# DAC.net
KiCad netlist of a schematic drawn in Altium Designer
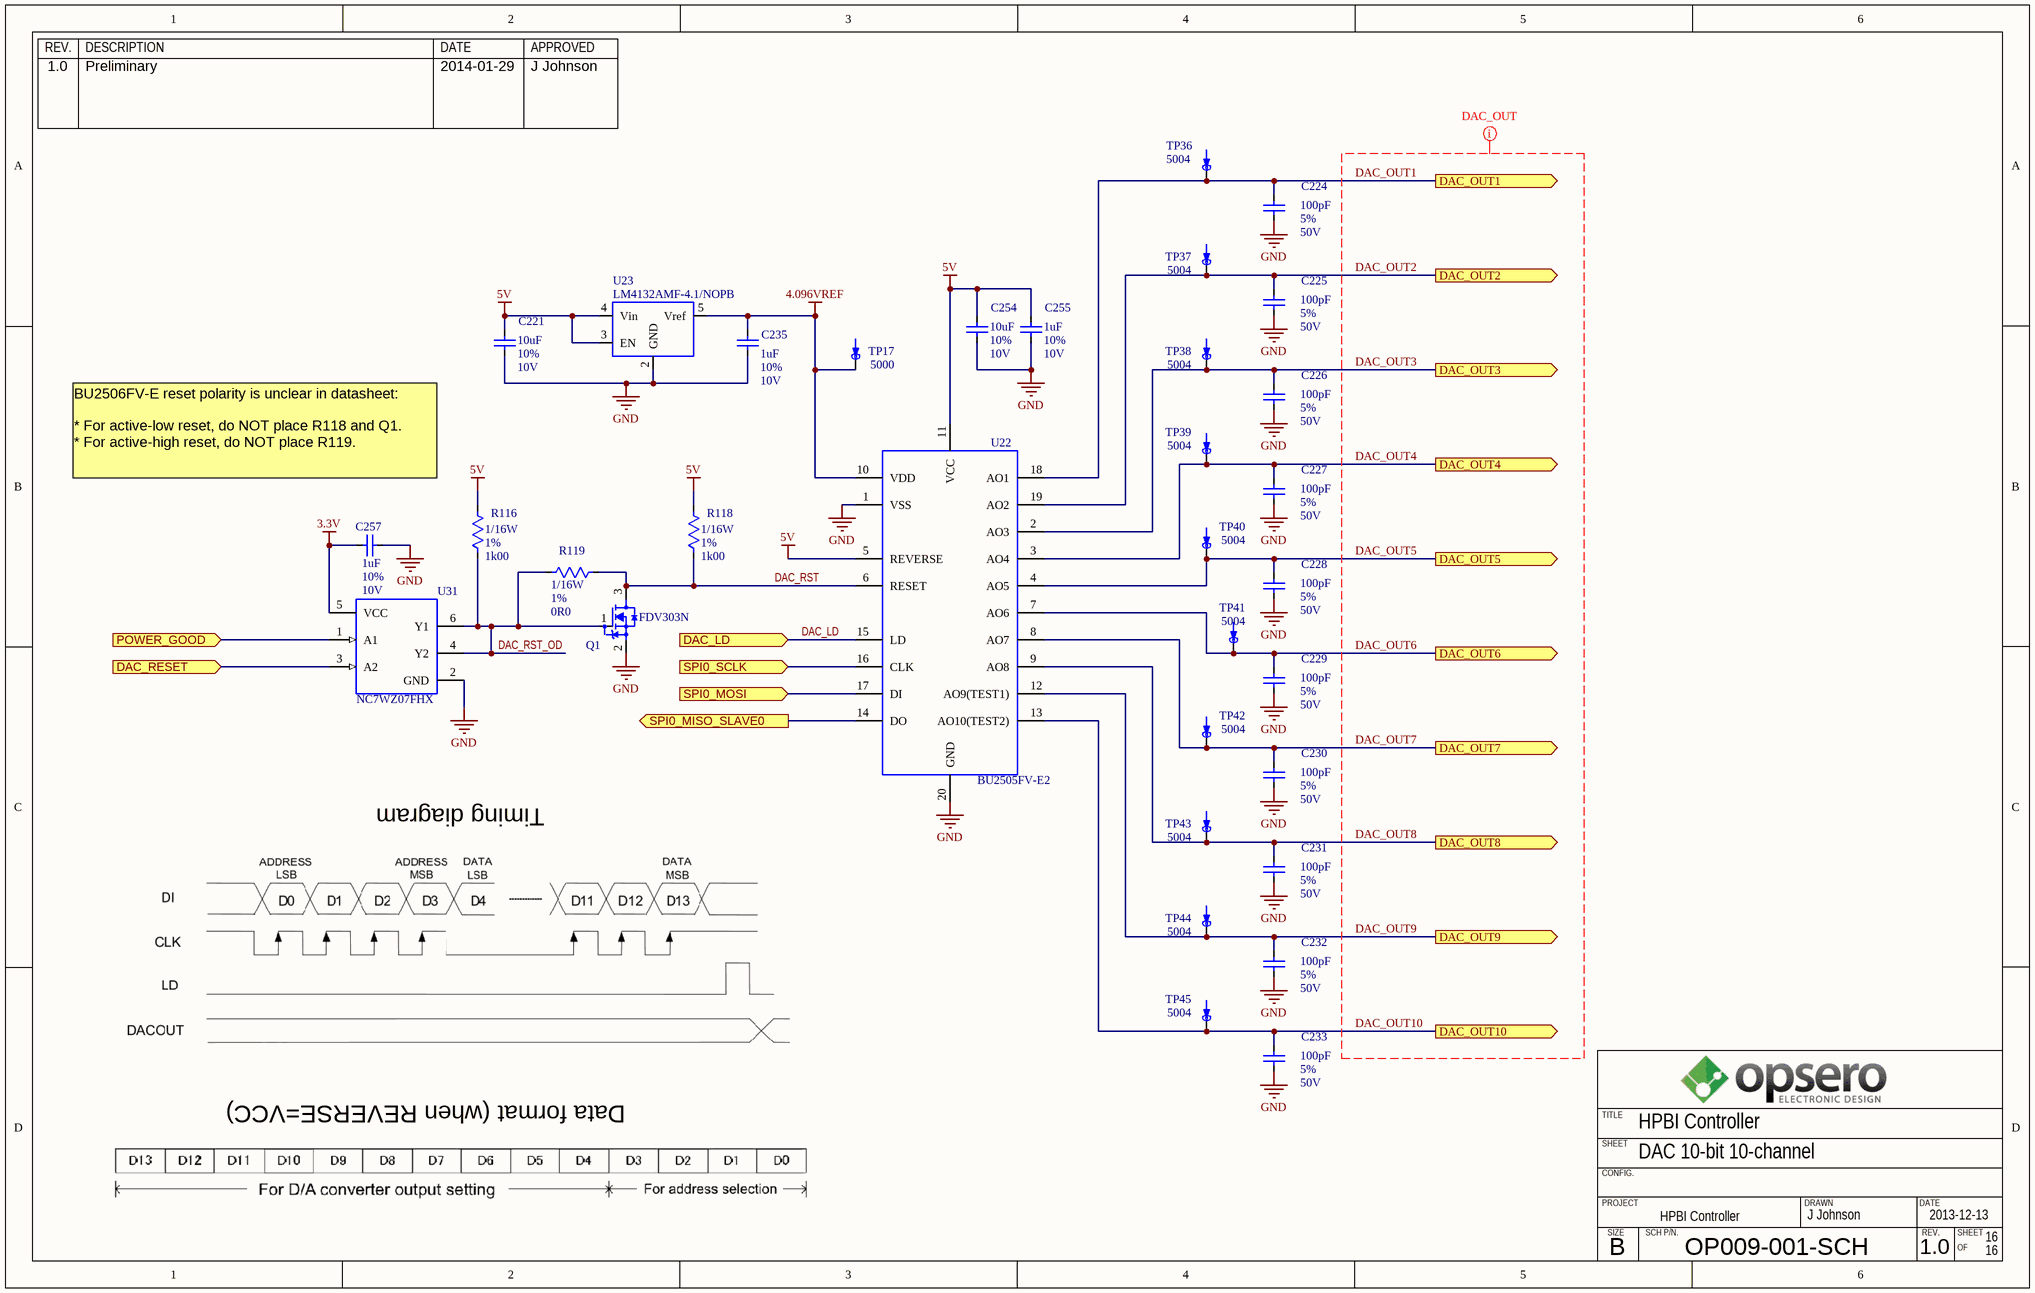
[diagram p0: DAC.SchDoc]

(export (version "E")
  (design (tool "Eeschema 10.0.6"))
  (components
    (comp (ref "C221")
      (value "10uF")
      (footprint "CAPC1608X38N")
      (description "Capacitor ceramic, X5R, 10uF, 10V, 10%, -55 to +85 C, EIA0603")
      (fields
        (field (name "TOLERANCE") "10%")
        (field (name "VOLTAGE") "10V")
        (field (name "Comment") "CAPACITOR_NP_TYPE1")
      )
      (libsource (lib "parts") (part "CAPACITOR_NP_TYPE1"))
    )
    (comp (ref "C224")
      (value "100pF")
      (footprint "CAPC1005X33N")
      (description "Capacitor ceramic, C0G (NP0), 100pF, 50V, 5%, -55 to +125 C, EIA0402")
      (fields
        (field (name "TOLERANCE") "5%")
        (field (name "VOLTAGE") "50V")
        (field (name "Comment") "CAPACITOR_NP_TYPE1")
      )
      (libsource (lib "parts") (part "CAPACITOR_NP_TYPE1"))
    )
    (comp (ref "C225")
      (value "100pF")
      (footprint "CAPC1005X33N")
      (description "Capacitor ceramic, C0G (NP0), 100pF, 50V, 5%, -55 to +125 C, EIA0402")
      (fields
        (field (name "TOLERANCE") "5%")
        (field (name "VOLTAGE") "50V")
        (field (name "Comment") "CAPACITOR_NP_TYPE1")
      )
      (libsource (lib "parts") (part "CAPACITOR_NP_TYPE1"))
    )
    (comp (ref "C226")
      (value "100pF")
      (footprint "CAPC1005X33N")
      (description "Capacitor ceramic, C0G (NP0), 100pF, 50V, 5%, -55 to +125 C, EIA0402")
      (fields
        (field (name "TOLERANCE") "5%")
        (field (name "VOLTAGE") "50V")
        (field (name "Comment") "CAPACITOR_NP_TYPE1")
      )
      (libsource (lib "parts") (part "CAPACITOR_NP_TYPE1"))
    )
    (comp (ref "C227")
      (value "100pF")
      (footprint "CAPC1005X33N")
      (description "Capacitor ceramic, C0G (NP0), 100pF, 50V, 5%, -55 to +125 C, EIA0402")
      (fields
        (field (name "TOLERANCE") "5%")
        (field (name "VOLTAGE") "50V")
        (field (name "Comment") "CAPACITOR_NP_TYPE1")
      )
      (libsource (lib "parts") (part "CAPACITOR_NP_TYPE1"))
    )
    (comp (ref "C228")
      (value "100pF")
      (footprint "CAPC1005X33N")
      (description "Capacitor ceramic, C0G (NP0), 100pF, 50V, 5%, -55 to +125 C, EIA0402")
      (fields
        (field (name "TOLERANCE") "5%")
        (field (name "VOLTAGE") "50V")
        (field (name "Comment") "CAPACITOR_NP_TYPE1")
      )
      (libsource (lib "parts") (part "CAPACITOR_NP_TYPE1"))
    )
    (comp (ref "C229")
      (value "100pF")
      (footprint "CAPC1005X33N")
      (description "Capacitor ceramic, C0G (NP0), 100pF, 50V, 5%, -55 to +125 C, EIA0402")
      (fields
        (field (name "TOLERANCE") "5%")
        (field (name "VOLTAGE") "50V")
        (field (name "Comment") "CAPACITOR_NP_TYPE1")
      )
      (libsource (lib "parts") (part "CAPACITOR_NP_TYPE1"))
    )
    (comp (ref "C230")
      (value "100pF")
      (footprint "CAPC1005X33N")
      (description "Capacitor ceramic, C0G (NP0), 100pF, 50V, 5%, -55 to +125 C, EIA0402")
      (fields
        (field (name "TOLERANCE") "5%")
        (field (name "VOLTAGE") "50V")
        (field (name "Comment") "CAPACITOR_NP_TYPE1")
      )
      (libsource (lib "parts") (part "CAPACITOR_NP_TYPE1"))
    )
    (comp (ref "C231")
      (value "100pF")
      (footprint "CAPC1005X33N")
      (description "Capacitor ceramic, C0G (NP0), 100pF, 50V, 5%, -55 to +125 C, EIA0402")
      (fields
        (field (name "TOLERANCE") "5%")
        (field (name "VOLTAGE") "50V")
        (field (name "Comment") "CAPACITOR_NP_TYPE1")
      )
      (libsource (lib "parts") (part "CAPACITOR_NP_TYPE1"))
    )
    (comp (ref "C232")
      (value "100pF")
      (footprint "CAPC1005X33N")
      (description "Capacitor ceramic, C0G (NP0), 100pF, 50V, 5%, -55 to +125 C, EIA0402")
      (fields
        (field (name "TOLERANCE") "5%")
        (field (name "VOLTAGE") "50V")
        (field (name "Comment") "CAPACITOR_NP_TYPE1")
      )
      (libsource (lib "parts") (part "CAPACITOR_NP_TYPE1"))
    )
    (comp (ref "C233")
      (value "100pF")
      (footprint "CAPC1005X33N")
      (description "Capacitor ceramic, C0G (NP0), 100pF, 50V, 5%, -55 to +125 C, EIA0402")
      (fields
        (field (name "TOLERANCE") "5%")
        (field (name "VOLTAGE") "50V")
        (field (name "Comment") "CAPACITOR_NP_TYPE1")
      )
      (libsource (lib "parts") (part "CAPACITOR_NP_TYPE1"))
    )
    (comp (ref "C235")
      (value "1uF")
      (footprint "CAPC1005X33N")
      (description "Capacitor ceramic, X5R, 1uF, 10V, 10%, -55 to +85 C, EIA0402")
      (fields
        (field (name "TOLERANCE") "10%")
        (field (name "VOLTAGE") "10V")
        (field (name "Comment") "CAPACITOR_NP_TYPE1")
      )
      (libsource (lib "parts") (part "CAPACITOR_NP_TYPE1"))
    )
    (comp (ref "C254")
      (value "10uF")
      (footprint "CAPC1608X38N")
      (description "Capacitor ceramic, X5R, 10uF, 10V, 10%, -55 to +85 C, EIA0603")
      (fields
        (field (name "TOLERANCE") "10%")
        (field (name "VOLTAGE") "10V")
        (field (name "Comment") "CAPACITOR_NP_TYPE1")
      )
      (libsource (lib "parts") (part "CAPACITOR_NP_TYPE1"))
    )
    (comp (ref "C255")
      (value "1uF")
      (footprint "CAPC1005X33N")
      (description "Capacitor ceramic, X5R, 1uF, 10V, 10%, -55 to +85 C, EIA0402")
      (fields
        (field (name "TOLERANCE") "10%")
        (field (name "VOLTAGE") "10V")
        (field (name "Comment") "CAPACITOR_NP_TYPE1")
      )
      (libsource (lib "parts") (part "CAPACITOR_NP_TYPE1"))
    )
    (comp (ref "C257")
      (value "1uF")
      (footprint "CAPC1005X33N")
      (description "Capacitor ceramic, X5R, 1uF, 10V, 10%, -55 to +85 C, EIA0402")
      (fields
        (field (name "TOLERANCE") "10%")
        (field (name "VOLTAGE") "10V")
        (field (name "Comment") "CAPACITOR_NP_TYPE1")
      )
      (libsource (lib "parts") (part "CAPACITOR_NP_TYPE1"))
    )
    (comp (ref "Q1")
      (value "TRANS_MOSFET_N-CH_TYPE1")
      (footprint "SOT95P240X110-3N")
      (description "Transistor MOSFET, digital FET, N-Channel, 25V, 680mA, -55 to +150 C, 350mW, SOT-23")
      (fields
        (field (name "POWER") "350mW")
        (field (name "VOLTAGE") "25V")
        (field (name "MFG PART NUMBER 1") "FDV303N")
      )
      (libsource (lib "parts") (part "TRANS_MOSFET_N-CH_TYPE1"))
    )
    (comp (ref "R116")
      (value "1k00")
      (footprint "RESC1005X33N")
      (description "Resistor, 1k00, 1/16W, 1%, -55 to +155 C, EIA0402")
      (fields (field (name "VOLTAGE") "50V") (field (name "POWER") "1/16W") (field (name "TOLERANCE") "1%"))
      (libsource (lib "parts") (part "RESISTOR_TYPE1"))
    )
    (comp (ref "R118")
      (value "1k00")
      (footprint "RESC1005X33N")
      (description "Resistor, 1k00, 1/16W, 1%, -55 to +155 C, EIA0402")
      (fields (field (name "VOLTAGE") "50V") (field (name "POWER") "1/16W") (field (name "TOLERANCE") "1%"))
      (libsource (lib "parts") (part "RESISTOR_TYPE1"))
    )
    (comp (ref "R119")
      (value "0R0")
      (footprint "RESC1005X33N")
      (description "Resistor, 0R0, 1/16W, 1%, -50 to +155 C, EIA0402, EIA(M)1005")
      (fields (field (name "VOLTAGE") "50V") (field (name "POWER") "1/16W") (field (name "TOLERANCE") "1%"))
      (libsource (lib "parts") (part "RESISTOR_TYPE1"))
    )
    (comp (ref "TP17")
      (value "5000")
      (footprint "KEY_5000")
      (description "Test point bead, red, Keystone Electronics, Thru-hole,")
      (fields (field (name "POWER") "Pow") (field (name "VOLTAGE") "Vol"))
      (libsource (lib "parts") (part "TEST_POINT_TYPE4"))
    )
    (comp (ref "TP36")
      (value "5004")
      (footprint "KEY_5004")
      (description "Test point bead, yellow, Keystone Electronics, Thru-hole,")
      (fields (field (name "POWER") "Pow") (field (name "VOLTAGE") "Vol"))
      (libsource (lib "parts") (part "TEST_POINT_TYPE4"))
    )
    (comp (ref "TP37")
      (value "5004")
      (footprint "KEY_5004")
      (description "Test point bead, yellow, Keystone Electronics, Thru-hole,")
      (fields (field (name "POWER") "Pow") (field (name "VOLTAGE") "Vol"))
      (libsource (lib "parts") (part "TEST_POINT_TYPE4"))
    )
    (comp (ref "TP38")
      (value "5004")
      (footprint "KEY_5004")
      (description "Test point bead, yellow, Keystone Electronics, Thru-hole,")
      (fields (field (name "POWER") "Pow") (field (name "VOLTAGE") "Vol"))
      (libsource (lib "parts") (part "TEST_POINT_TYPE4"))
    )
    (comp (ref "TP39")
      (value "5004")
      (footprint "KEY_5004")
      (description "Test point bead, yellow, Keystone Electronics, Thru-hole,")
      (fields (field (name "POWER") "Pow") (field (name "VOLTAGE") "Vol"))
      (libsource (lib "parts") (part "TEST_POINT_TYPE4"))
    )
    (comp (ref "TP40")
      (value "5004")
      (footprint "KEY_5004")
      (description "Test point bead, yellow, Keystone Electronics, Thru-hole,")
      (fields (field (name "POWER") "Pow") (field (name "VOLTAGE") "Vol"))
      (libsource (lib "parts") (part "TEST_POINT_TYPE4"))
    )
    (comp (ref "TP41")
      (value "5004")
      (footprint "KEY_5004")
      (description "Test point bead, yellow, Keystone Electronics, Thru-hole,")
      (fields (field (name "POWER") "Pow") (field (name "VOLTAGE") "Vol"))
      (libsource (lib "parts") (part "TEST_POINT_TYPE4"))
    )
    (comp (ref "TP42")
      (value "5004")
      (footprint "KEY_5004")
      (description "Test point bead, yellow, Keystone Electronics, Thru-hole,")
      (fields (field (name "POWER") "Pow") (field (name "VOLTAGE") "Vol"))
      (libsource (lib "parts") (part "TEST_POINT_TYPE4"))
    )
    (comp (ref "TP43")
      (value "5004")
      (footprint "KEY_5004")
      (description "Test point bead, yellow, Keystone Electronics, Thru-hole,")
      (fields (field (name "POWER") "Pow") (field (name "VOLTAGE") "Vol"))
      (libsource (lib "parts") (part "TEST_POINT_TYPE4"))
    )
    (comp (ref "TP44")
      (value "5004")
      (footprint "KEY_5004")
      (description "Test point bead, yellow, Keystone Electronics, Thru-hole,")
      (fields (field (name "POWER") "Pow") (field (name "VOLTAGE") "Vol"))
      (libsource (lib "parts") (part "TEST_POINT_TYPE4"))
    )
    (comp (ref "TP45")
      (value "5004")
      (footprint "KEY_5004")
      (description "Test point bead, yellow, Keystone Electronics, Thru-hole,")
      (fields (field (name "POWER") "Pow") (field (name "VOLTAGE") "Vol"))
      (libsource (lib "parts") (part "TEST_POINT_TYPE4"))
    )
    (comp (ref "U22")
      (value "BU2505FV-E2")
      (footprint "SSOP65P440X650X115-20N")
      (description "DAC 10 bit, High precision, 10 channel, 4.5 to 5.5V, -30 to +85C")
      (libsource (lib "parts") (part "BU2505FV-E2"))
    )
    (comp (ref "U23")
      (value "LM4132")
      (footprint "SOT65P280X145-5AN")
      (description "Reference 4.096V low dropout, 20mA, 10ppm, 0.05%")
      (fields
        (field (name "POWER") "Pow")
        (field (name "TOLERANCE") "±0.05%")
        (field (name "MFG PART NUMBER 1") "LM4132AMF-4.1/NOPB")
      )
      (libsource (lib "parts") (part "LM4132"))
    )
    (comp (ref "U31")
      (value "NC7WZ07FHX")
      (footprint "DFN35P100X100X55-6N")
      (description "UHS Dual Buffer, Tiny Logic, 1.65 to 5.5V, -40 to +85 C, 200mW, MicroPak2-6")
      (fields
        (field (name "POWER") "Pow")
        (field (name "VOLTAGE") "1.65 to 5.5V")
        (field (name "MFG PART NUMBER 1") "NC7WZ07FHX")
      )
      (libsource (lib "parts") (part "NC7WZ07FHX"))
    )
  )
  (nets
    (net (code "1") (name "/DAC_LD") (class "Default")
      (node (ref "U22") (pin "15") (pinfunction "LD_15") (pintype "passive"))
    )
    (net (code "2") (name "/DAC_OUT1") (class "Default")
      (node (ref "C224") (pin "1") (pinfunction "1_1") (pintype "passive"))
      (node (ref "TP36") (pin "1") (pinfunction "1_1") (pintype "passive"))
      (node (ref "U22") (pin "18") (pinfunction "AO1_18") (pintype "passive"))
    )
    (net (code "3") (name "/DAC_OUT2") (class "Default")
      (node (ref "C225") (pin "1") (pinfunction "1_1") (pintype "passive"))
      (node (ref "TP37") (pin "1") (pinfunction "1_1") (pintype "passive"))
      (node (ref "U22") (pin "19") (pinfunction "AO2_19") (pintype "passive"))
    )
    (net (code "4") (name "/DAC_OUT3") (class "Default")
      (node (ref "C226") (pin "1") (pinfunction "1_1") (pintype "passive"))
      (node (ref "TP38") (pin "1") (pinfunction "1_1") (pintype "passive"))
      (node (ref "U22") (pin "2") (pinfunction "AO3_2") (pintype "passive"))
    )
    (net (code "5") (name "/DAC_OUT4") (class "Default")
      (node (ref "C227") (pin "1") (pinfunction "1_1") (pintype "passive"))
      (node (ref "TP39") (pin "1") (pinfunction "1_1") (pintype "passive"))
      (node (ref "U22") (pin "3") (pinfunction "AO4_3") (pintype "passive"))
    )
    (net (code "6") (name "/DAC_OUT5") (class "Default")
      (node (ref "C228") (pin "1") (pinfunction "1_1") (pintype "passive"))
      (node (ref "TP40") (pin "1") (pinfunction "1_1") (pintype "passive"))
      (node (ref "U22") (pin "4") (pinfunction "AO5_4") (pintype "passive"))
    )
    (net (code "7") (name "/DAC_OUT6") (class "Default")
      (node (ref "C229") (pin "1") (pinfunction "1_1") (pintype "passive"))
      (node (ref "TP41") (pin "1") (pinfunction "1_1") (pintype "passive"))
      (node (ref "U22") (pin "7") (pinfunction "AO6_7") (pintype "passive"))
    )
    (net (code "8") (name "/DAC_OUT7") (class "Default")
      (node (ref "C230") (pin "1") (pinfunction "1_1") (pintype "passive"))
      (node (ref "TP42") (pin "1") (pinfunction "1_1") (pintype "passive"))
      (node (ref "U22") (pin "8") (pinfunction "AO7_8") (pintype "passive"))
    )
    (net (code "9") (name "/DAC_OUT8") (class "Default")
      (node (ref "C231") (pin "1") (pinfunction "1_1") (pintype "passive"))
      (node (ref "TP43") (pin "1") (pinfunction "1_1") (pintype "passive"))
      (node (ref "U22") (pin "9") (pinfunction "AO8_9") (pintype "passive"))
    )
    (net (code "10") (name "/DAC_OUT9") (class "Default")
      (node (ref "C232") (pin "1") (pinfunction "1_1") (pintype "passive"))
      (node (ref "TP44") (pin "1") (pinfunction "1_1") (pintype "passive"))
      (node (ref "U22") (pin "12") (pinfunction "AO9(TEST1)_12") (pintype "passive"))
    )
    (net (code "11") (name "/DAC_OUT10") (class "Default")
      (node (ref "C233") (pin "1") (pinfunction "1_1") (pintype "passive"))
      (node (ref "TP45") (pin "1") (pinfunction "1_1") (pintype "passive"))
      (node (ref "U22") (pin "13") (pinfunction "AO10(TEST2)_13") (pintype "passive"))
    )
    (net (code "12") (name "/DAC_RESET") (class "Default")
      (node (ref "U31") (pin "3") (pinfunction "A2_3") (pintype "input"))
    )
    (net (code "13") (name "/DAC_RST") (class "Default")
      (node (ref "Q1") (pin "3") (pinfunction "D_3") (pintype "passive"))
      (node (ref "R118") (pin "1") (pinfunction "1_1") (pintype "passive"))
      (node (ref "R119") (pin "2") (pinfunction "2_2") (pintype "passive"))
      (node (ref "U22") (pin "6") (pinfunction "RESET_6") (pintype "passive"))
    )
    (net (code "14") (name "/DAC_RST_OD") (class "Default")
      (node (ref "Q1") (pin "1") (pinfunction "G_1") (pintype "passive"))
      (node (ref "R116") (pin "1") (pinfunction "1_1") (pintype "passive"))
      (node (ref "R119") (pin "1") (pinfunction "1_1") (pintype "passive"))
      (node (ref "U31") (pin "4") (pinfunction "Y2_4") (pintype "open_collector"))
      (node (ref "U31") (pin "6") (pinfunction "Y1_6") (pintype "open_collector"))
    )
    (net (code "15") (name "/POWER_GOOD") (class "Default")
      (node (ref "U31") (pin "1") (pinfunction "A1_1") (pintype "input"))
    )
    (net (code "16") (name "/SPI0_MISO_SLAVE0") (class "Default")
      (node (ref "U22") (pin "14") (pinfunction "DO_14") (pintype "passive"))
    )
    (net (code "17") (name "/SPI0_MOSI") (class "Default")
      (node (ref "U22") (pin "17") (pinfunction "DI_17") (pintype "passive"))
    )
    (net (code "18") (name "/SPI0_SCLK") (class "Default")
      (node (ref "U22") (pin "16") (pinfunction "CLK_16") (pintype "passive"))
    )
    (net (code "19") (name "3.3V") (class "Default")
      (node (ref "C257") (pin "1") (pinfunction "1_1") (pintype "passive"))
      (node (ref "U31") (pin "5") (pinfunction "VCC_5") (pintype "power_in"))
    )
    (net (code "20") (name "4.096VREF") (class "Default")
      (node (ref "C235") (pin "1") (pinfunction "1_1") (pintype "passive"))
      (node (ref "TP17") (pin "1") (pinfunction "1_1") (pintype "passive"))
      (node (ref "U22") (pin "10") (pinfunction "VDD_10") (pintype "passive"))
      (node (ref "U23") (pin "5") (pinfunction "Vref_5") (pintype "power_in"))
    )
    (net (code "21") (name "5V") (class "Default")
      (node (ref "C221") (pin "1") (pinfunction "1_1") (pintype "passive"))
      (node (ref "C254") (pin "1") (pinfunction "1_1") (pintype "passive"))
      (node (ref "C255") (pin "1") (pinfunction "1_1") (pintype "passive"))
      (node (ref "R116") (pin "2") (pinfunction "2_2") (pintype "passive"))
      (node (ref "R118") (pin "2") (pinfunction "2_2") (pintype "passive"))
      (node (ref "U22") (pin "11") (pinfunction "VCC_11") (pintype "passive"))
      (node (ref "U22") (pin "5") (pinfunction "REVERSE_5") (pintype "passive"))
      (node (ref "U23") (pin "3") (pinfunction "EN_3") (pintype "passive"))
      (node (ref "U23") (pin "4") (pinfunction "Vin_4") (pintype "power_in"))
    )
    (net (code "22") (name "GND") (class "Default")
      (node (ref "C221") (pin "2") (pinfunction "2_2") (pintype "passive"))
      (node (ref "C224") (pin "2") (pinfunction "2_2") (pintype "passive"))
      (node (ref "C225") (pin "2") (pinfunction "2_2") (pintype "passive"))
      (node (ref "C226") (pin "2") (pinfunction "2_2") (pintype "passive"))
      (node (ref "C227") (pin "2") (pinfunction "2_2") (pintype "passive"))
      (node (ref "C228") (pin "2") (pinfunction "2_2") (pintype "passive"))
      (node (ref "C229") (pin "2") (pinfunction "2_2") (pintype "passive"))
      (node (ref "C230") (pin "2") (pinfunction "2_2") (pintype "passive"))
      (node (ref "C231") (pin "2") (pinfunction "2_2") (pintype "passive"))
      (node (ref "C232") (pin "2") (pinfunction "2_2") (pintype "passive"))
      (node (ref "C233") (pin "2") (pinfunction "2_2") (pintype "passive"))
      (node (ref "C235") (pin "2") (pinfunction "2_2") (pintype "passive"))
      (node (ref "C254") (pin "2") (pinfunction "2_2") (pintype "passive"))
      (node (ref "C255") (pin "2") (pinfunction "2_2") (pintype "passive"))
      (node (ref "C257") (pin "2") (pinfunction "2_2") (pintype "passive"))
      (node (ref "Q1") (pin "2") (pinfunction "S_2") (pintype "passive"))
      (node (ref "U22") (pin "1") (pinfunction "VSS_1") (pintype "passive"))
      (node (ref "U22") (pin "20") (pinfunction "GND_20") (pintype "passive"))
      (node (ref "U23") (pin "2") (pinfunction "GND_2") (pintype "power_in"))
      (node (ref "U31") (pin "2") (pinfunction "GND_2") (pintype "power_in"))
    )
  )
)
